# LED.net
KiCad netlist of a schematic drawn in EAGLE
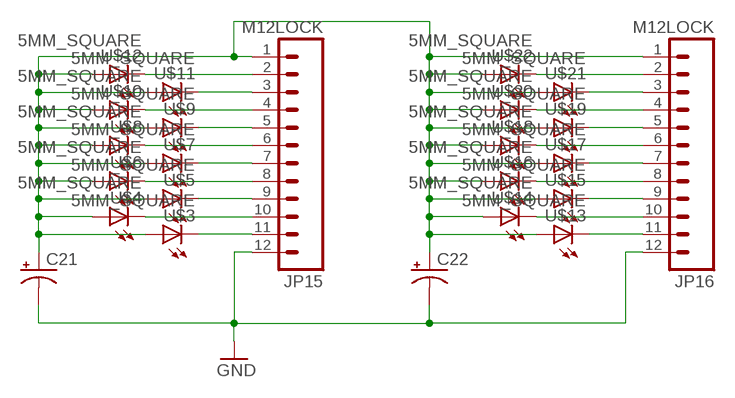
[diagram p0: schematic, sheet 1]

(export (version "E")
  (design (tool "Eeschema 10.0.6"))
  (components
    (comp (ref "C21")
      (value "CPOL-USE2-5")
      (footprint "eagle-import:E2-5")
      (libsource (lib "eagle-import") (part "CPOL-USE2-5"))
    )
    (comp (ref "C22")
      (value "CPOL-USE2-5")
      (footprint "eagle-import:E2-5")
      (libsource (lib "eagle-import") (part "CPOL-USE2-5"))
    )
    (comp (ref "JP15")
      (value "M12LOCK")
      (footprint "eagle-import:1X12_LOCK")
      (libsource (lib "eagle-import") (part "M12LOCK"))
    )
    (comp (ref "JP16")
      (value "M12LOCK")
      (footprint "eagle-import:1X12_LOCK")
      (libsource (lib "eagle-import") (part "M12LOCK"))
    )
    (comp (ref "U$3")
      (value "5MM_SQUARE")
      (footprint "eagle-import:5MM_SQUARE")
      (libsource (lib "eagle-import") (part "5MM_SQUARE"))
    )
    (comp (ref "U$4")
      (value "5MM_SQUARE")
      (footprint "eagle-import:5MM_SQUARE")
      (libsource (lib "eagle-import") (part "5MM_SQUARE"))
    )
    (comp (ref "U$5")
      (value "5MM_SQUARE")
      (footprint "eagle-import:5MM_SQUARE")
      (libsource (lib "eagle-import") (part "5MM_SQUARE"))
    )
    (comp (ref "U$6")
      (value "5MM_SQUARE")
      (footprint "eagle-import:5MM_SQUARE")
      (libsource (lib "eagle-import") (part "5MM_SQUARE"))
    )
    (comp (ref "U$7")
      (value "5MM_SQUARE")
      (footprint "eagle-import:5MM_SQUARE")
      (libsource (lib "eagle-import") (part "5MM_SQUARE"))
    )
    (comp (ref "U$8")
      (value "5MM_SQUARE")
      (footprint "eagle-import:5MM_SQUARE")
      (libsource (lib "eagle-import") (part "5MM_SQUARE"))
    )
    (comp (ref "U$9")
      (value "5MM_SQUARE")
      (footprint "eagle-import:5MM_SQUARE")
      (libsource (lib "eagle-import") (part "5MM_SQUARE"))
    )
    (comp (ref "U$10")
      (value "5MM_SQUARE")
      (footprint "eagle-import:5MM_SQUARE")
      (libsource (lib "eagle-import") (part "5MM_SQUARE"))
    )
    (comp (ref "U$11")
      (value "5MM_SQUARE")
      (footprint "eagle-import:5MM_SQUARE")
      (libsource (lib "eagle-import") (part "5MM_SQUARE"))
    )
    (comp (ref "U$12")
      (value "5MM_SQUARE")
      (footprint "eagle-import:5MM_SQUARE")
      (libsource (lib "eagle-import") (part "5MM_SQUARE"))
    )
    (comp (ref "U$13")
      (value "5MM_SQUARE")
      (footprint "eagle-import:5MM_SQUARE")
      (libsource (lib "eagle-import") (part "5MM_SQUARE"))
    )
    (comp (ref "U$14")
      (value "5MM_SQUARE")
      (footprint "eagle-import:5MM_SQUARE")
      (libsource (lib "eagle-import") (part "5MM_SQUARE"))
    )
    (comp (ref "U$15")
      (value "5MM_SQUARE")
      (footprint "eagle-import:5MM_SQUARE")
      (libsource (lib "eagle-import") (part "5MM_SQUARE"))
    )
    (comp (ref "U$16")
      (value "5MM_SQUARE")
      (footprint "eagle-import:5MM_SQUARE")
      (libsource (lib "eagle-import") (part "5MM_SQUARE"))
    )
    (comp (ref "U$17")
      (value "5MM_SQUARE")
      (footprint "eagle-import:5MM_SQUARE")
      (libsource (lib "eagle-import") (part "5MM_SQUARE"))
    )
    (comp (ref "U$18")
      (value "5MM_SQUARE")
      (footprint "eagle-import:5MM_SQUARE")
      (libsource (lib "eagle-import") (part "5MM_SQUARE"))
    )
    (comp (ref "U$19")
      (value "5MM_SQUARE")
      (footprint "eagle-import:5MM_SQUARE")
      (libsource (lib "eagle-import") (part "5MM_SQUARE"))
    )
    (comp (ref "U$20")
      (value "5MM_SQUARE")
      (footprint "eagle-import:5MM_SQUARE")
      (libsource (lib "eagle-import") (part "5MM_SQUARE"))
    )
    (comp (ref "U$21")
      (value "5MM_SQUARE")
      (footprint "eagle-import:5MM_SQUARE")
      (libsource (lib "eagle-import") (part "5MM_SQUARE"))
    )
    (comp (ref "U$22")
      (value "5MM_SQUARE")
      (footprint "eagle-import:5MM_SQUARE")
      (libsource (lib "eagle-import") (part "5MM_SQUARE"))
    )
  )
  (nets
    (net (code "1") (name "GND") (class "Default")
      (node (ref "C21") (pin "-") (pinfunction "-_-") (pintype "passive"))
      (node (ref "C22") (pin "-") (pinfunction "-_-") (pintype "passive"))
      (node (ref "JP15") (pin "12") (pinfunction "12_12") (pintype "passive"))
      (node (ref "JP16") (pin "12") (pinfunction "12_12") (pintype "passive"))
    )
    (net (code "2") (name "Net-(U$3-C)") (class "Default")
      (node (ref "JP15") (pin "11") (pinfunction "11_11") (pintype "passive"))
      (node (ref "U$3") (pin "N") (pinfunction "C_N") (pintype "passive"))
    )
    (net (code "3") (name "Net-(U$4-C)") (class "Default")
      (node (ref "JP15") (pin "10") (pinfunction "10_10") (pintype "passive"))
      (node (ref "U$4") (pin "N") (pinfunction "C_N") (pintype "passive"))
    )
    (net (code "4") (name "Net-(U$5-C)") (class "Default")
      (node (ref "JP15") (pin "9") (pinfunction "9_9") (pintype "passive"))
      (node (ref "U$5") (pin "N") (pinfunction "C_N") (pintype "passive"))
    )
    (net (code "5") (name "Net-(U$6-C)") (class "Default")
      (node (ref "JP15") (pin "8") (pinfunction "8_8") (pintype "passive"))
      (node (ref "U$6") (pin "N") (pinfunction "C_N") (pintype "passive"))
    )
    (net (code "6") (name "Net-(U$7-C)") (class "Default")
      (node (ref "JP15") (pin "7") (pinfunction "7_7") (pintype "passive"))
      (node (ref "U$7") (pin "N") (pinfunction "C_N") (pintype "passive"))
    )
    (net (code "7") (name "Net-(U$8-C)") (class "Default")
      (node (ref "JP15") (pin "6") (pinfunction "6_6") (pintype "passive"))
      (node (ref "U$8") (pin "N") (pinfunction "C_N") (pintype "passive"))
    )
    (net (code "8") (name "Net-(U$9-C)") (class "Default")
      (node (ref "JP15") (pin "5") (pinfunction "5_5") (pintype "passive"))
      (node (ref "U$9") (pin "N") (pinfunction "C_N") (pintype "passive"))
    )
    (net (code "9") (name "Net-(U$10-A)") (class "Default")
      (node (ref "C21") (pin "+") (pinfunction "+_+") (pintype "passive"))
      (node (ref "C22") (pin "+") (pinfunction "+_+") (pintype "passive"))
      (node (ref "JP15") (pin "1") (pinfunction "1_1") (pintype "passive"))
      (node (ref "JP16") (pin "1") (pinfunction "1_1") (pintype "passive"))
      (node (ref "U$10") (pin "P") (pinfunction "A_P") (pintype "passive"))
      (node (ref "U$11") (pin "P") (pinfunction "A_P") (pintype "passive"))
      (node (ref "U$12") (pin "P") (pinfunction "A_P") (pintype "passive"))
      (node (ref "U$13") (pin "P") (pinfunction "A_P") (pintype "passive"))
      (node (ref "U$14") (pin "P") (pinfunction "A_P") (pintype "passive"))
      (node (ref "U$15") (pin "P") (pinfunction "A_P") (pintype "passive"))
      (node (ref "U$16") (pin "P") (pinfunction "A_P") (pintype "passive"))
      (node (ref "U$17") (pin "P") (pinfunction "A_P") (pintype "passive"))
      (node (ref "U$18") (pin "P") (pinfunction "A_P") (pintype "passive"))
      (node (ref "U$19") (pin "P") (pinfunction "A_P") (pintype "passive"))
      (node (ref "U$20") (pin "P") (pinfunction "A_P") (pintype "passive"))
      (node (ref "U$21") (pin "P") (pinfunction "A_P") (pintype "passive"))
      (node (ref "U$22") (pin "P") (pinfunction "A_P") (pintype "passive"))
      (node (ref "U$3") (pin "P") (pinfunction "A_P") (pintype "passive"))
      (node (ref "U$4") (pin "P") (pinfunction "A_P") (pintype "passive"))
      (node (ref "U$5") (pin "P") (pinfunction "A_P") (pintype "passive"))
      (node (ref "U$6") (pin "P") (pinfunction "A_P") (pintype "passive"))
      (node (ref "U$7") (pin "P") (pinfunction "A_P") (pintype "passive"))
      (node (ref "U$8") (pin "P") (pinfunction "A_P") (pintype "passive"))
      (node (ref "U$9") (pin "P") (pinfunction "A_P") (pintype "passive"))
    )
    (net (code "10") (name "Net-(U$10-C)") (class "Default")
      (node (ref "JP15") (pin "4") (pinfunction "4_4") (pintype "passive"))
      (node (ref "U$10") (pin "N") (pinfunction "C_N") (pintype "passive"))
    )
    (net (code "11") (name "Net-(U$11-C)") (class "Default")
      (node (ref "JP15") (pin "3") (pinfunction "3_3") (pintype "passive"))
      (node (ref "U$11") (pin "N") (pinfunction "C_N") (pintype "passive"))
    )
    (net (code "12") (name "Net-(U$12-C)") (class "Default")
      (node (ref "JP15") (pin "2") (pinfunction "2_2") (pintype "passive"))
      (node (ref "U$12") (pin "N") (pinfunction "C_N") (pintype "passive"))
    )
    (net (code "13") (name "Net-(U$13-C)") (class "Default")
      (node (ref "JP16") (pin "11") (pinfunction "11_11") (pintype "passive"))
      (node (ref "U$13") (pin "N") (pinfunction "C_N") (pintype "passive"))
    )
    (net (code "14") (name "Net-(U$14-C)") (class "Default")
      (node (ref "JP16") (pin "10") (pinfunction "10_10") (pintype "passive"))
      (node (ref "U$14") (pin "N") (pinfunction "C_N") (pintype "passive"))
    )
    (net (code "15") (name "Net-(U$15-C)") (class "Default")
      (node (ref "JP16") (pin "9") (pinfunction "9_9") (pintype "passive"))
      (node (ref "U$15") (pin "N") (pinfunction "C_N") (pintype "passive"))
    )
    (net (code "16") (name "Net-(U$16-C)") (class "Default")
      (node (ref "JP16") (pin "8") (pinfunction "8_8") (pintype "passive"))
      (node (ref "U$16") (pin "N") (pinfunction "C_N") (pintype "passive"))
    )
    (net (code "17") (name "Net-(U$17-C)") (class "Default")
      (node (ref "JP16") (pin "7") (pinfunction "7_7") (pintype "passive"))
      (node (ref "U$17") (pin "N") (pinfunction "C_N") (pintype "passive"))
    )
    (net (code "18") (name "Net-(U$18-C)") (class "Default")
      (node (ref "JP16") (pin "6") (pinfunction "6_6") (pintype "passive"))
      (node (ref "U$18") (pin "N") (pinfunction "C_N") (pintype "passive"))
    )
    (net (code "19") (name "Net-(U$19-C)") (class "Default")
      (node (ref "JP16") (pin "5") (pinfunction "5_5") (pintype "passive"))
      (node (ref "U$19") (pin "N") (pinfunction "C_N") (pintype "passive"))
    )
    (net (code "20") (name "Net-(U$20-C)") (class "Default")
      (node (ref "JP16") (pin "4") (pinfunction "4_4") (pintype "passive"))
      (node (ref "U$20") (pin "N") (pinfunction "C_N") (pintype "passive"))
    )
    (net (code "21") (name "Net-(U$21-C)") (class "Default")
      (node (ref "JP16") (pin "3") (pinfunction "3_3") (pintype "passive"))
      (node (ref "U$21") (pin "N") (pinfunction "C_N") (pintype "passive"))
    )
    (net (code "22") (name "Net-(U$22-C)") (class "Default")
      (node (ref "JP16") (pin "2") (pinfunction "2_2") (pintype "passive"))
      (node (ref "U$22") (pin "N") (pinfunction "C_N") (pintype "passive"))
    )
  )
)
